# RH037_2.net
KiCad netlist of a schematic drawn in EAGLE
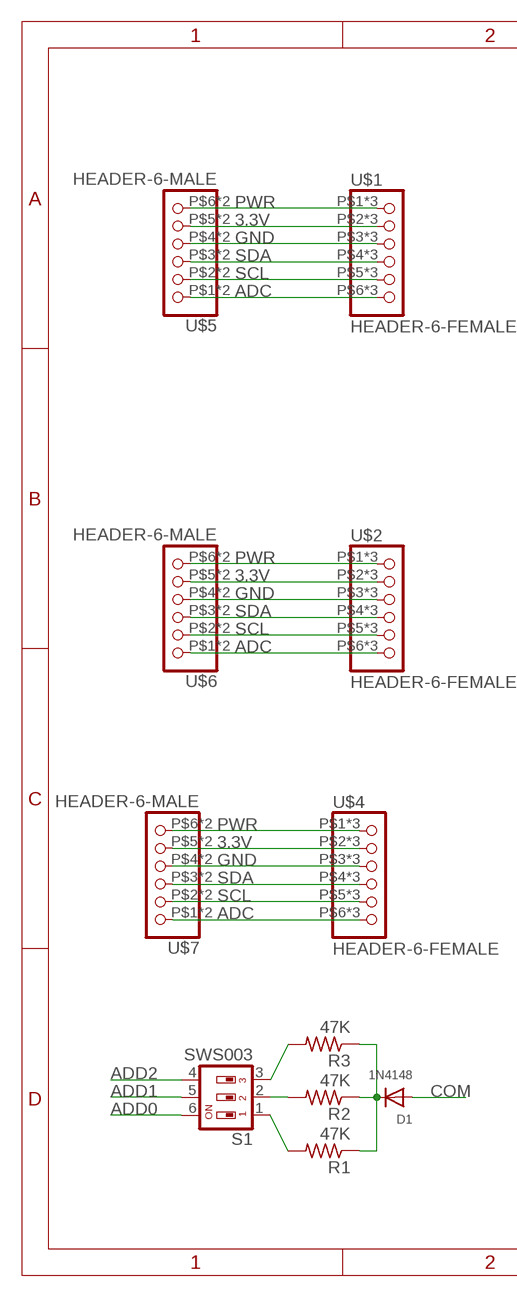
[diagram p0: schematic, sheet 1, part 1 of 2]
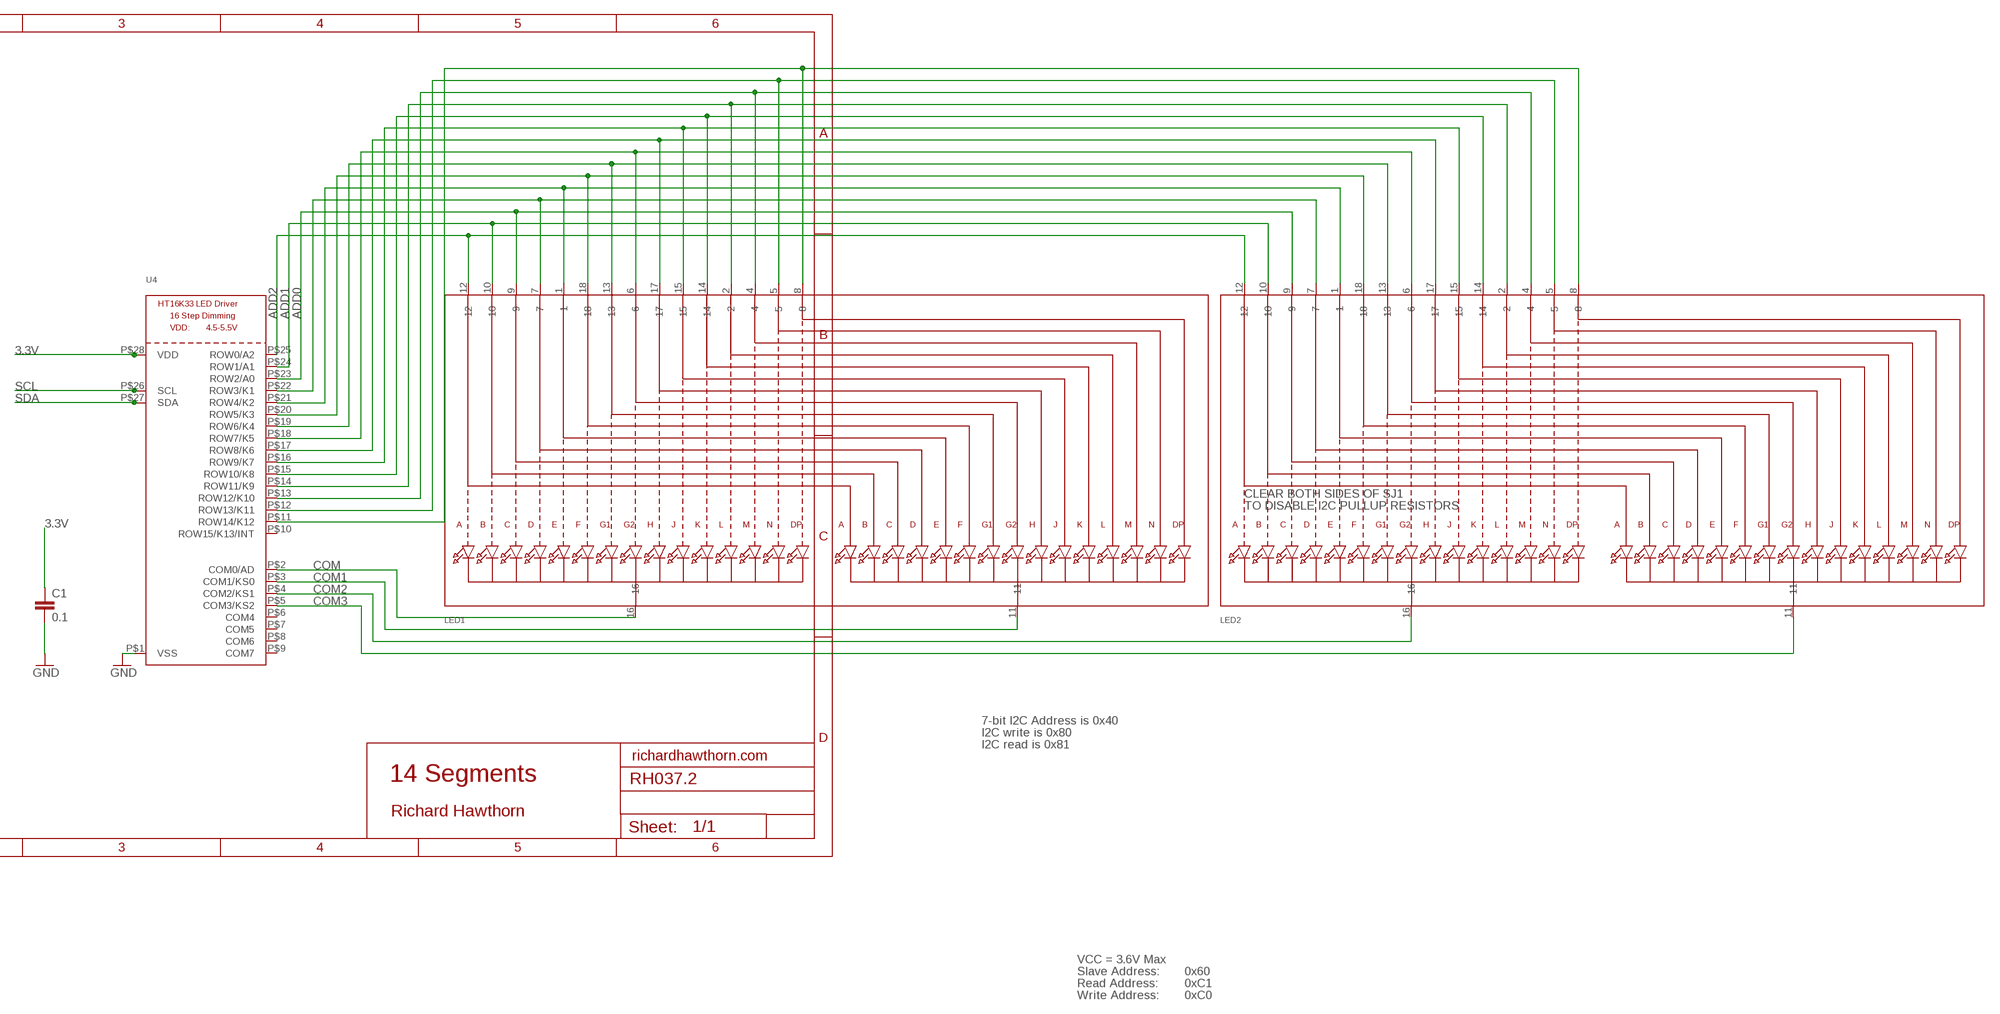
[diagram p1: schematic, sheet 1, part 2 of 2]

(export (version "E")
  (design (tool "Eeschema 10.0.6"))
  (components
    (comp (ref "C1")
      (value "0.1")
      (footprint "eagle-import:0603-CAP")
      (libsource (lib "eagle-import") (part "CAP0603-CAP"))
    )
    (comp (ref "D1")
      (value "1N4148")
      (footprint "eagle-import:SOD-323F")
      (libsource (lib "eagle-import") (part "DIODESOD-323F"))
    )
    (comp (ref "LED1")
      (value "DISP_SEGMENT_STARBURST_DUAL_COMMONCATHODE")
      (footprint "eagle-import:SEGMENT_STARTBUST_DUAL_KWA-541CBB")
      (libsource (lib "eagle-import") (part "DISP_SEGMENT_STARBURST_DUAL_COMMONCATHODE"))
    )
    (comp (ref "LED2")
      (value "DISP_SEGMENT_STARBURST_DUAL_COMMONCATHODE")
      (footprint "eagle-import:SEGMENT_STARTBUST_DUAL_KWA-541CBB")
      (libsource (lib "eagle-import") (part "DISP_SEGMENT_STARBURST_DUAL_COMMONCATHODE"))
    )
    (comp (ref "R1")
      (value "47K")
      (footprint "eagle-import:R0805")
      (libsource (lib "eagle-import") (part "R-US_R0805"))
    )
    (comp (ref "R2")
      (value "47K")
      (footprint "eagle-import:R0805")
      (libsource (lib "eagle-import") (part "R-US_R0805"))
    )
    (comp (ref "R3")
      (value "47K")
      (footprint "eagle-import:R0805")
      (libsource (lib "eagle-import") (part "R-US_R0805"))
    )
    (comp (ref "S1")
      (value "SWS003")
      (footprint "eagle-import:SMS-003")
      (libsource (lib "eagle-import") (part "SWS003"))
    )
    (comp (ref "U$1")
      (value "HEADER-6-FEMALE")
      (footprint "eagle-import:2MMHEADER6")
      (libsource (lib "eagle-import") (part "HEADER-6-FEMALE"))
    )
    (comp (ref "U$2")
      (value "HEADER-6-FEMALE")
      (footprint "eagle-import:2MMHEADER6")
      (libsource (lib "eagle-import") (part "HEADER-6-FEMALE"))
    )
    (comp (ref "U$4")
      (value "HEADER-6-FEMALE")
      (footprint "eagle-import:2MMHEADER6")
      (libsource (lib "eagle-import") (part "HEADER-6-FEMALE"))
    )
    (comp (ref "U$5")
      (value "HEADER-6-MALE")
      (footprint "eagle-import:2MMHEADERPIN6")
      (libsource (lib "eagle-import") (part "HEADER-6-MALE"))
    )
    (comp (ref "U$6")
      (value "HEADER-6-MALE")
      (footprint "eagle-import:2MMHEADERPIN6")
      (libsource (lib "eagle-import") (part "HEADER-6-MALE"))
    )
    (comp (ref "U$7")
      (value "HEADER-6-MALE")
      (footprint "eagle-import:2MMHEADERPIN6")
      (libsource (lib "eagle-import") (part "HEADER-6-MALE"))
    )
    (comp (ref "U4")
      (value "HT16K33_SOP28")
      (footprint "eagle-import:SOP28_300MIL")
      (libsource (lib "eagle-import") (part "HT16K33_SOP28"))
    )
  )
  (nets
    (net (code "1") (name "/3.3V") (class "Default")
      (node (ref "C1") (pin "1") (pinfunction "1_1") (pintype "passive"))
      (node (ref "U$1") (pin "P$10") (pinfunction "2_P$10") (pintype "passive"))
      (node (ref "U$1") (pin "P$18") (pinfunction "2_P$18") (pintype "passive"))
      (node (ref "U$1") (pin "P$2") (pinfunction "2_P$2") (pintype "passive"))
      (node (ref "U$2") (pin "P$10") (pinfunction "2_P$10") (pintype "passive"))
      (node (ref "U$2") (pin "P$18") (pinfunction "2_P$18") (pintype "passive"))
      (node (ref "U$2") (pin "P$2") (pinfunction "2_P$2") (pintype "passive"))
      (node (ref "U$4") (pin "P$10") (pinfunction "2_P$10") (pintype "passive"))
      (node (ref "U$4") (pin "P$18") (pinfunction "2_P$18") (pintype "passive"))
      (node (ref "U$4") (pin "P$2") (pinfunction "2_P$2") (pintype "passive"))
      (node (ref "U$5") (pin "P$13") (pinfunction "5_P$13") (pintype "passive"))
      (node (ref "U$5") (pin "P$5") (pinfunction "5_P$5") (pintype "passive"))
      (node (ref "U$6") (pin "P$13") (pinfunction "5_P$13") (pintype "passive"))
      (node (ref "U$6") (pin "P$5") (pinfunction "5_P$5") (pintype "passive"))
      (node (ref "U$7") (pin "P$13") (pinfunction "5_P$13") (pintype "passive"))
      (node (ref "U$7") (pin "P$5") (pinfunction "5_P$5") (pintype "passive"))
      (node (ref "U4") (pin "P$28") (pinfunction "VDD_P$28") (pintype "bidirectional"))
    )
    (net (code "2") (name "/ADC") (class "Default")
      (node (ref "U$1") (pin "P$14") (pinfunction "6_P$14") (pintype "passive"))
      (node (ref "U$1") (pin "P$22") (pinfunction "6_P$22") (pintype "passive"))
      (node (ref "U$1") (pin "P$6") (pinfunction "6_P$6") (pintype "passive"))
      (node (ref "U$2") (pin "P$14") (pinfunction "6_P$14") (pintype "passive"))
      (node (ref "U$2") (pin "P$22") (pinfunction "6_P$22") (pintype "passive"))
      (node (ref "U$2") (pin "P$6") (pinfunction "6_P$6") (pintype "passive"))
      (node (ref "U$4") (pin "P$14") (pinfunction "6_P$14") (pintype "passive"))
      (node (ref "U$4") (pin "P$22") (pinfunction "6_P$22") (pintype "passive"))
      (node (ref "U$4") (pin "P$6") (pinfunction "6_P$6") (pintype "passive"))
      (node (ref "U$5") (pin "P$1") (pinfunction "1_P$1") (pintype "passive"))
      (node (ref "U$5") (pin "P$9") (pinfunction "1_P$9") (pintype "passive"))
      (node (ref "U$6") (pin "P$1") (pinfunction "1_P$1") (pintype "passive"))
      (node (ref "U$6") (pin "P$9") (pinfunction "1_P$9") (pintype "passive"))
      (node (ref "U$7") (pin "P$1") (pinfunction "1_P$1") (pintype "passive"))
      (node (ref "U$7") (pin "P$9") (pinfunction "1_P$9") (pintype "passive"))
    )
    (net (code "3") (name "/ADD0") (class "Default")
      (node (ref "LED1") (pin "9") (pinfunction "9_9") (pintype "bidirectional"))
      (node (ref "LED2") (pin "9") (pinfunction "9_9") (pintype "bidirectional"))
      (node (ref "S1") (pin "6") (pinfunction "6_6") (pintype "passive"))
      (node (ref "U4") (pin "P$23") (pinfunction "ROW2/A0_P$23") (pintype "bidirectional"))
    )
    (net (code "4") (name "/ADD1") (class "Default")
      (node (ref "LED1") (pin "10") (pinfunction "10_10") (pintype "bidirectional"))
      (node (ref "LED2") (pin "10") (pinfunction "10_10") (pintype "bidirectional"))
      (node (ref "S1") (pin "5") (pinfunction "5_5") (pintype "passive"))
      (node (ref "U4") (pin "P$24") (pinfunction "ROW1/A1_P$24") (pintype "bidirectional"))
    )
    (net (code "5") (name "/ADD2") (class "Default")
      (node (ref "LED1") (pin "12") (pinfunction "12_12") (pintype "bidirectional"))
      (node (ref "LED2") (pin "12") (pinfunction "12_12") (pintype "bidirectional"))
      (node (ref "S1") (pin "4") (pinfunction "4_4") (pintype "passive"))
      (node (ref "U4") (pin "P$25") (pinfunction "ROW0/A2_P$25") (pintype "bidirectional"))
    )
    (net (code "6") (name "/COM") (class "Default")
      (node (ref "D1") (pin "A") (pinfunction "A_A") (pintype "passive"))
      (node (ref "LED1") (pin "16") (pinfunction "16_16") (pintype "bidirectional"))
      (node (ref "U4") (pin "P$2") (pinfunction "COM0/AD_P$2") (pintype "bidirectional"))
    )
    (net (code "7") (name "/COM1") (class "Default")
      (node (ref "LED1") (pin "11") (pinfunction "11_11") (pintype "bidirectional"))
      (node (ref "U4") (pin "P$3") (pinfunction "COM1/KS0_P$3") (pintype "bidirectional"))
    )
    (net (code "8") (name "/COM2") (class "Default")
      (node (ref "LED2") (pin "16") (pinfunction "16_16") (pintype "bidirectional"))
      (node (ref "U4") (pin "P$4") (pinfunction "COM2/KS1_P$4") (pintype "bidirectional"))
    )
    (net (code "9") (name "/COM3") (class "Default")
      (node (ref "LED2") (pin "11") (pinfunction "11_11") (pintype "bidirectional"))
      (node (ref "U4") (pin "P$5") (pinfunction "COM3/KS2_P$5") (pintype "bidirectional"))
    )
    (net (code "10") (name "/PWR") (class "Default")
      (node (ref "U$1") (pin "P$1") (pinfunction "1_P$1") (pintype "passive"))
      (node (ref "U$1") (pin "P$17") (pinfunction "1_P$17") (pintype "passive"))
      (node (ref "U$1") (pin "P$9") (pinfunction "1_P$9") (pintype "passive"))
      (node (ref "U$2") (pin "P$1") (pinfunction "1_P$1") (pintype "passive"))
      (node (ref "U$2") (pin "P$17") (pinfunction "1_P$17") (pintype "passive"))
      (node (ref "U$2") (pin "P$9") (pinfunction "1_P$9") (pintype "passive"))
      (node (ref "U$4") (pin "P$1") (pinfunction "1_P$1") (pintype "passive"))
      (node (ref "U$4") (pin "P$17") (pinfunction "1_P$17") (pintype "passive"))
      (node (ref "U$4") (pin "P$9") (pinfunction "1_P$9") (pintype "passive"))
      (node (ref "U$5") (pin "P$14") (pinfunction "6_P$14") (pintype "passive"))
      (node (ref "U$5") (pin "P$6") (pinfunction "6_P$6") (pintype "passive"))
      (node (ref "U$6") (pin "P$14") (pinfunction "6_P$14") (pintype "passive"))
      (node (ref "U$6") (pin "P$6") (pinfunction "6_P$6") (pintype "passive"))
      (node (ref "U$7") (pin "P$14") (pinfunction "6_P$14") (pintype "passive"))
      (node (ref "U$7") (pin "P$6") (pinfunction "6_P$6") (pintype "passive"))
    )
    (net (code "11") (name "/SCL") (class "Default")
      (node (ref "U$1") (pin "P$13") (pinfunction "5_P$13") (pintype "passive"))
      (node (ref "U$1") (pin "P$21") (pinfunction "5_P$21") (pintype "passive"))
      (node (ref "U$1") (pin "P$5") (pinfunction "5_P$5") (pintype "passive"))
      (node (ref "U$2") (pin "P$13") (pinfunction "5_P$13") (pintype "passive"))
      (node (ref "U$2") (pin "P$21") (pinfunction "5_P$21") (pintype "passive"))
      (node (ref "U$2") (pin "P$5") (pinfunction "5_P$5") (pintype "passive"))
      (node (ref "U$4") (pin "P$13") (pinfunction "5_P$13") (pintype "passive"))
      (node (ref "U$4") (pin "P$21") (pinfunction "5_P$21") (pintype "passive"))
      (node (ref "U$4") (pin "P$5") (pinfunction "5_P$5") (pintype "passive"))
      (node (ref "U$5") (pin "P$10") (pinfunction "2_P$10") (pintype "passive"))
      (node (ref "U$5") (pin "P$2") (pinfunction "2_P$2") (pintype "passive"))
      (node (ref "U$6") (pin "P$10") (pinfunction "2_P$10") (pintype "passive"))
      (node (ref "U$6") (pin "P$2") (pinfunction "2_P$2") (pintype "passive"))
      (node (ref "U$7") (pin "P$10") (pinfunction "2_P$10") (pintype "passive"))
      (node (ref "U$7") (pin "P$2") (pinfunction "2_P$2") (pintype "passive"))
      (node (ref "U4") (pin "P$26") (pinfunction "SCL_P$26") (pintype "bidirectional"))
    )
    (net (code "12") (name "/SDA") (class "Default")
      (node (ref "U$1") (pin "P$12") (pinfunction "4_P$12") (pintype "passive"))
      (node (ref "U$1") (pin "P$20") (pinfunction "4_P$20") (pintype "passive"))
      (node (ref "U$1") (pin "P$4") (pinfunction "4_P$4") (pintype "passive"))
      (node (ref "U$2") (pin "P$12") (pinfunction "4_P$12") (pintype "passive"))
      (node (ref "U$2") (pin "P$20") (pinfunction "4_P$20") (pintype "passive"))
      (node (ref "U$2") (pin "P$4") (pinfunction "4_P$4") (pintype "passive"))
      (node (ref "U$4") (pin "P$12") (pinfunction "4_P$12") (pintype "passive"))
      (node (ref "U$4") (pin "P$20") (pinfunction "4_P$20") (pintype "passive"))
      (node (ref "U$4") (pin "P$4") (pinfunction "4_P$4") (pintype "passive"))
      (node (ref "U$5") (pin "P$11") (pinfunction "3_P$11") (pintype "passive"))
      (node (ref "U$5") (pin "P$3") (pinfunction "3_P$3") (pintype "passive"))
      (node (ref "U$6") (pin "P$11") (pinfunction "3_P$11") (pintype "passive"))
      (node (ref "U$6") (pin "P$3") (pinfunction "3_P$3") (pintype "passive"))
      (node (ref "U$7") (pin "P$11") (pinfunction "3_P$11") (pintype "passive"))
      (node (ref "U$7") (pin "P$3") (pinfunction "3_P$3") (pintype "passive"))
      (node (ref "U4") (pin "P$27") (pinfunction "SDA_P$27") (pintype "bidirectional"))
    )
    (net (code "13") (name "GND") (class "Default")
      (node (ref "C1") (pin "2") (pinfunction "2_2") (pintype "passive"))
      (node (ref "U$1") (pin "P$11") (pinfunction "3_P$11") (pintype "passive"))
      (node (ref "U$1") (pin "P$19") (pinfunction "3_P$19") (pintype "passive"))
      (node (ref "U$1") (pin "P$3") (pinfunction "3_P$3") (pintype "passive"))
      (node (ref "U$2") (pin "P$11") (pinfunction "3_P$11") (pintype "passive"))
      (node (ref "U$2") (pin "P$19") (pinfunction "3_P$19") (pintype "passive"))
      (node (ref "U$2") (pin "P$3") (pinfunction "3_P$3") (pintype "passive"))
      (node (ref "U$4") (pin "P$11") (pinfunction "3_P$11") (pintype "passive"))
      (node (ref "U$4") (pin "P$19") (pinfunction "3_P$19") (pintype "passive"))
      (node (ref "U$4") (pin "P$3") (pinfunction "3_P$3") (pintype "passive"))
      (node (ref "U$5") (pin "P$12") (pinfunction "4_P$12") (pintype "passive"))
      (node (ref "U$5") (pin "P$4") (pinfunction "4_P$4") (pintype "passive"))
      (node (ref "U$6") (pin "P$12") (pinfunction "4_P$12") (pintype "passive"))
      (node (ref "U$6") (pin "P$4") (pinfunction "4_P$4") (pintype "passive"))
      (node (ref "U$7") (pin "P$12") (pinfunction "4_P$12") (pintype "passive"))
      (node (ref "U$7") (pin "P$4") (pinfunction "4_P$4") (pintype "passive"))
      (node (ref "U4") (pin "P$1") (pinfunction "VSS_P$1") (pintype "bidirectional"))
    )
    (net (code "14") (name "Net-(D1-PadC)") (class "Default")
      (node (ref "D1") (pin "C") (pinfunction "C_C") (pintype "passive"))
      (node (ref "R1") (pin "1") (pinfunction "1_1") (pintype "passive"))
      (node (ref "R2") (pin "1") (pinfunction "1_1") (pintype "passive"))
      (node (ref "R3") (pin "1") (pinfunction "1_1") (pintype "passive"))
    )
    (net (code "15") (name "Net-(R1-Pad2)") (class "Default")
      (node (ref "R1") (pin "2") (pinfunction "2_2") (pintype "passive"))
      (node (ref "S1") (pin "1") (pinfunction "1_1") (pintype "passive"))
    )
    (net (code "16") (name "Net-(R2-Pad2)") (class "Default")
      (node (ref "R2") (pin "2") (pinfunction "2_2") (pintype "passive"))
      (node (ref "S1") (pin "2") (pinfunction "2_2") (pintype "passive"))
    )
    (net (code "17") (name "Net-(R3-Pad2)") (class "Default")
      (node (ref "R3") (pin "2") (pinfunction "2_2") (pintype "passive"))
      (node (ref "S1") (pin "3") (pinfunction "3_3") (pintype "passive"))
    )
    (net (code "18") (name "Net-(U4-ROW3{slash}K1)") (class "Default")
      (node (ref "LED1") (pin "7") (pinfunction "7_7") (pintype "bidirectional"))
      (node (ref "LED2") (pin "7") (pinfunction "7_7") (pintype "bidirectional"))
      (node (ref "U4") (pin "P$22") (pinfunction "ROW3/K1_P$22") (pintype "bidirectional"))
    )
    (net (code "19") (name "Net-(U4-ROW4{slash}K2)") (class "Default")
      (node (ref "LED1") (pin "1") (pinfunction "1_1") (pintype "bidirectional"))
      (node (ref "LED2") (pin "1") (pinfunction "1_1") (pintype "bidirectional"))
      (node (ref "U4") (pin "P$21") (pinfunction "ROW4/K2_P$21") (pintype "bidirectional"))
    )
    (net (code "20") (name "Net-(U4-ROW5{slash}K3)") (class "Default")
      (node (ref "LED1") (pin "18") (pinfunction "18_18") (pintype "bidirectional"))
      (node (ref "LED2") (pin "18") (pinfunction "18_18") (pintype "bidirectional"))
      (node (ref "U4") (pin "P$20") (pinfunction "ROW5/K3_P$20") (pintype "bidirectional"))
    )
    (net (code "21") (name "Net-(U4-ROW6{slash}K4)") (class "Default")
      (node (ref "LED1") (pin "13") (pinfunction "13_13") (pintype "bidirectional"))
      (node (ref "LED2") (pin "13") (pinfunction "13_13") (pintype "bidirectional"))
      (node (ref "U4") (pin "P$19") (pinfunction "ROW6/K4_P$19") (pintype "bidirectional"))
    )
    (net (code "22") (name "Net-(U4-ROW7{slash}K5)") (class "Default")
      (node (ref "LED1") (pin "6") (pinfunction "6_6") (pintype "bidirectional"))
      (node (ref "LED2") (pin "6") (pinfunction "6_6") (pintype "bidirectional"))
      (node (ref "U4") (pin "P$18") (pinfunction "ROW7/K5_P$18") (pintype "bidirectional"))
    )
    (net (code "23") (name "Net-(U4-ROW8{slash}K6)") (class "Default")
      (node (ref "LED1") (pin "17") (pinfunction "17_17") (pintype "bidirectional"))
      (node (ref "LED2") (pin "17") (pinfunction "17_17") (pintype "bidirectional"))
      (node (ref "U4") (pin "P$17") (pinfunction "ROW8/K6_P$17") (pintype "bidirectional"))
    )
    (net (code "24") (name "Net-(U4-ROW9{slash}K7)") (class "Default")
      (node (ref "LED1") (pin "15") (pinfunction "15_15") (pintype "bidirectional"))
      (node (ref "LED2") (pin "15") (pinfunction "15_15") (pintype "bidirectional"))
      (node (ref "U4") (pin "P$16") (pinfunction "ROW9/K7_P$16") (pintype "bidirectional"))
    )
    (net (code "25") (name "Net-(U4-ROW10{slash}K8)") (class "Default")
      (node (ref "LED1") (pin "14") (pinfunction "14_14") (pintype "bidirectional"))
      (node (ref "LED2") (pin "14") (pinfunction "14_14") (pintype "bidirectional"))
      (node (ref "U4") (pin "P$15") (pinfunction "ROW10/K8_P$15") (pintype "bidirectional"))
    )
    (net (code "26") (name "Net-(U4-ROW11{slash}K9)") (class "Default")
      (node (ref "LED1") (pin "2") (pinfunction "2_2") (pintype "bidirectional"))
      (node (ref "LED2") (pin "2") (pinfunction "2_2") (pintype "bidirectional"))
      (node (ref "U4") (pin "P$14") (pinfunction "ROW11/K9_P$14") (pintype "bidirectional"))
    )
    (net (code "27") (name "Net-(U4-ROW12{slash}K10)") (class "Default")
      (node (ref "LED1") (pin "4") (pinfunction "4_4") (pintype "bidirectional"))
      (node (ref "LED2") (pin "4") (pinfunction "4_4") (pintype "bidirectional"))
      (node (ref "U4") (pin "P$13") (pinfunction "ROW12/K10_P$13") (pintype "bidirectional"))
    )
    (net (code "28") (name "Net-(U4-ROW13{slash}K11)") (class "Default")
      (node (ref "LED1") (pin "5") (pinfunction "5_5") (pintype "bidirectional"))
      (node (ref "LED2") (pin "5") (pinfunction "5_5") (pintype "bidirectional"))
      (node (ref "U4") (pin "P$12") (pinfunction "ROW13/K11_P$12") (pintype "bidirectional"))
    )
    (net (code "29") (name "Net-(U4-ROW14{slash}K12)") (class "Default")
      (node (ref "LED1") (pin "8") (pinfunction "8_8") (pintype "bidirectional"))
      (node (ref "LED2") (pin "8") (pinfunction "8_8") (pintype "bidirectional"))
      (node (ref "U4") (pin "P$11") (pinfunction "ROW14/K12_P$11") (pintype "bidirectional"))
    )
    (net (code "30") (name "unconnected-(U4-COM4-PadP$6)") (class "Default")
      (node (ref "U4") (pin "P$6") (pinfunction "COM4_P$6") (pintype "bidirectional"))
    )
    (net (code "31") (name "unconnected-(U4-COM5-PadP$7)") (class "Default")
      (node (ref "U4") (pin "P$7") (pinfunction "COM5_P$7") (pintype "bidirectional"))
    )
    (net (code "32") (name "unconnected-(U4-COM6-PadP$8)") (class "Default")
      (node (ref "U4") (pin "P$8") (pinfunction "COM6_P$8") (pintype "bidirectional"))
    )
    (net (code "33") (name "unconnected-(U4-COM7-PadP$9)") (class "Default")
      (node (ref "U4") (pin "P$9") (pinfunction "COM7_P$9") (pintype "bidirectional"))
    )
    (net (code "34") (name "unconnected-(U4-ROW15{slash}K13{slash}INT-PadP$10)") (class "Default")
      (node (ref "U4") (pin "P$10") (pinfunction "ROW15/K13/INT_P$10") (pintype "bidirectional"))
    )
  )
)
